# STAND_ALONE_TEST.net
KiCad netlist of a schematic drawn in EAGLE
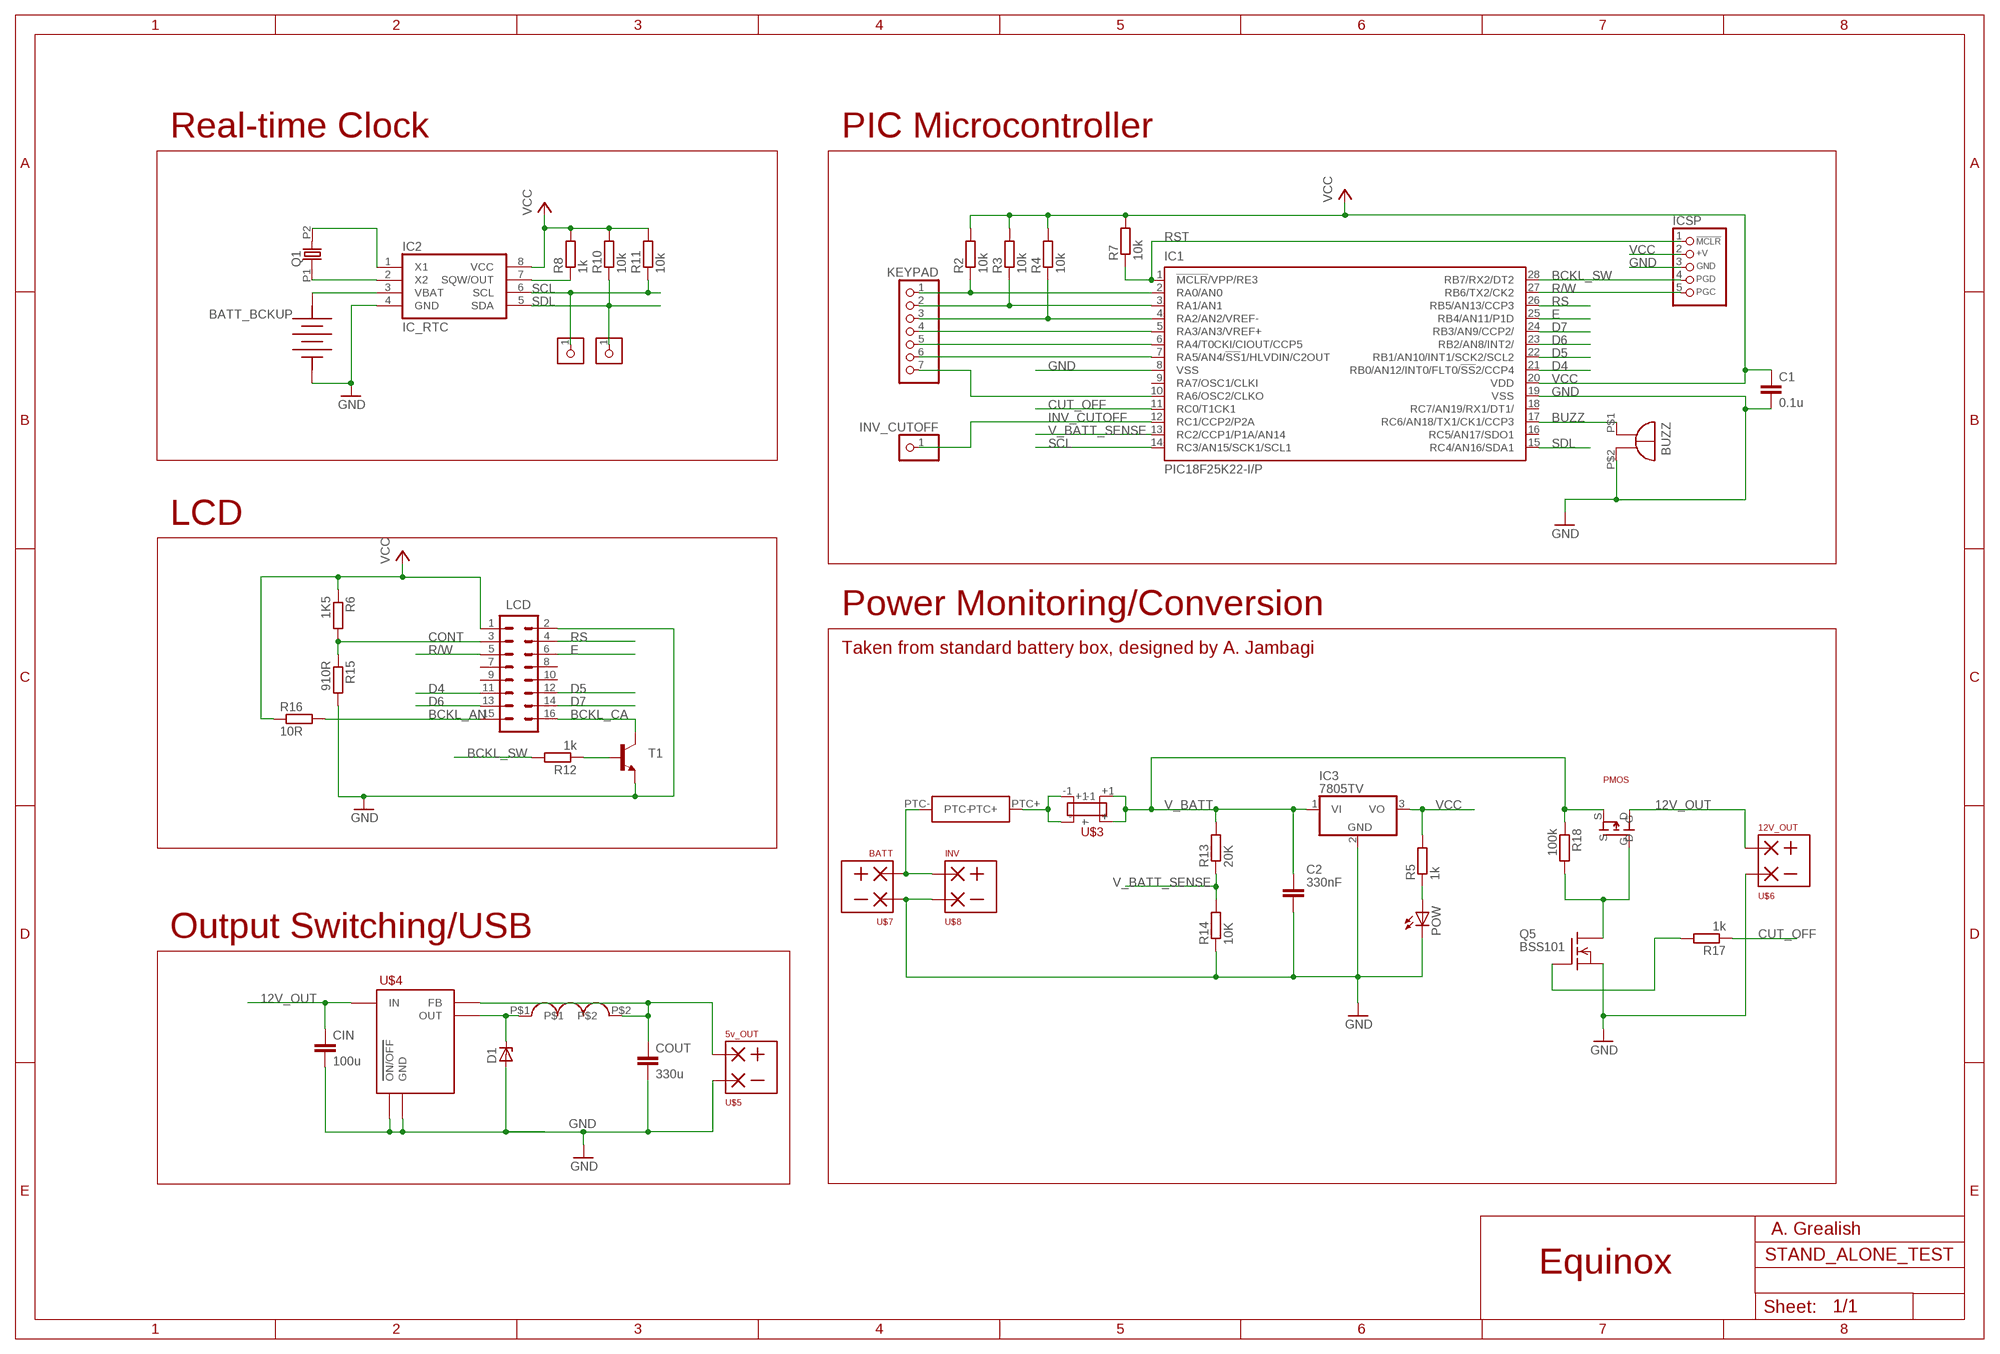
[diagram p0: schematic, sheet 1]

(export (version "E")
  (design (tool "Eeschema 10.0.6"))
  (components
    (comp (ref "BATT_BCKUP")
      (value "RENATA_COIN_CELL")
      (footprint "eagle-import:PANASONIC_CR2032_1298246")
      (libsource (lib "eagle-import") (part "PANASONIC_CR2032_1298246"))
    )
    (comp (ref "BUZZ")
      (value "BUZZ_14MM")
      (footprint "eagle-import:14MM_5M_PINS")
      (libsource (lib "eagle-import") (part "BUZZ_14MM"))
    )
    (comp (ref "C1")
      (value "0.1u")
      (footprint "eagle-import:CAP-PTH-SMALL2")
      (libsource (lib "eagle-import") (part "CAPPTH2"))
    )
    (comp (ref "C2")
      (value "330nF")
      (footprint "eagle-import:C0.1PTH")
      (libsource (lib "eagle-import") (part "CAPACITOR_NPOL-PTH_0.1{dblquote}"))
    )
    (comp (ref "CIN")
      (value "100u")
      (footprint "eagle-import:C2.5-2")
      (libsource (lib "eagle-import") (part "C2.5/2"))
    )
    (comp (ref "COUT")
      (value "330u")
      (footprint "eagle-import:C2.5-2")
      (libsource (lib "eagle-import") (part "C2.5/2"))
    )
    (comp (ref "D1")
      (value "ZENER-DIODEDO41Z10")
      (footprint "eagle-import:DO41Z10")
      (libsource (lib "eagle-import") (part "ZENER-DIODEDO41Z10"))
    )
    (comp (ref "IC1")
      (value "PIC18F25K22-I/P")
      (footprint "eagle-import:DIP28")
      (libsource (lib "eagle-import") (part "PIC18F25K22/P-I"))
    )
    (comp (ref "IC2")
      (value "IC_RTC")
      (footprint "eagle-import:DIP8")
      (libsource (lib "eagle-import") (part "IC_RTC_DS1307_DIP8"))
    )
    (comp (ref "IC3")
      (value "7805TV")
      (footprint "eagle-import:TO220V")
      (libsource (lib "eagle-import") (part "78TV05"))
    )
    (comp (ref "ICSP")
      (value "CON_HEADER_PRG_PIC_ICSPA")
      (footprint "eagle-import:HEADER_PRG_1X05")
      (libsource (lib "eagle-import") (part "CON_HEADER_PRG_PIC_ICSPA"))
    )
    (comp (ref "INV_CUTOFF")
      (value "PINHD-1X1")
      (footprint "eagle-import:1X01")
      (libsource (lib "eagle-import") (part "PINHD-1X1"))
    )
    (comp (ref "KEYPAD")
      (value "PINHD-1X7")
      (footprint "eagle-import:1X07")
      (libsource (lib "eagle-import") (part "PINHD-1X7"))
    )
    (comp (ref "LCD")
      (value "M08X2-SHROUDED_LOCK")
      (footprint "eagle-import:2X8-SHROUDED_LOCK")
      (libsource (lib "eagle-import") (part "M08X2-SHROUDED_LOCK"))
    )
    (comp (ref "PMOS")
      (value "PMOS")
      (footprint "eagle-import:NMOS_IPAK")
      (libsource (lib "eagle-import") (part "PMOS"))
    )
    (comp (ref "POW")
      (value "LED5MM")
      (footprint "eagle-import:LED5MM")
      (libsource (lib "eagle-import") (part "LED5MM"))
    )
    (comp (ref "Q1")
      (value "OSC-XTALTC-26")
      (footprint "eagle-import:TC-26")
      (libsource (lib "eagle-import") (part "OSC-XTALTC-26"))
    )
    (comp (ref "Q5")
      (value "BSS101")
      (footprint "eagle-import:TO92")
      (libsource (lib "eagle-import") (part "BSS101"))
    )
    (comp (ref "R2")
      (value "10k")
      (footprint "eagle-import:RTH025W")
      (libsource (lib "eagle-import") (part "RESISTOR-PTH-0.4"))
    )
    (comp (ref "R3")
      (value "10k")
      (footprint "eagle-import:RTH025W")
      (libsource (lib "eagle-import") (part "RESISTOR-PTH-0.4"))
    )
    (comp (ref "R4")
      (value "10k")
      (footprint "eagle-import:RTH025W")
      (libsource (lib "eagle-import") (part "RESISTOR-PTH-0.4"))
    )
    (comp (ref "R5")
      (value "1k")
      (footprint "eagle-import:RTH025W")
      (libsource (lib "eagle-import") (part "RESISTOR-PTH-0.4"))
    )
    (comp (ref "R6")
      (value "1K5")
      (footprint "eagle-import:RTH025W")
      (libsource (lib "eagle-import") (part "RESISTOR-PTH-0.4"))
    )
    (comp (ref "R7")
      (value "10k")
      (footprint "eagle-import:RTH025W")
      (libsource (lib "eagle-import") (part "RESISTOR-PTH-0.4"))
    )
    (comp (ref "R8")
      (value "1k")
      (footprint "eagle-import:RTH025W")
      (libsource (lib "eagle-import") (part "RESISTOR-PTH-0.4"))
    )
    (comp (ref "R10")
      (value "10k")
      (footprint "eagle-import:RTH025W")
      (libsource (lib "eagle-import") (part "RESISTOR-PTH-0.4"))
    )
    (comp (ref "R11")
      (value "10k")
      (footprint "eagle-import:RTH025W")
      (libsource (lib "eagle-import") (part "RESISTOR-PTH-0.4"))
    )
    (comp (ref "R12")
      (value "1k")
      (footprint "eagle-import:RTH025W")
      (libsource (lib "eagle-import") (part "RESISTOR-PTH-0.4"))
    )
    (comp (ref "R13")
      (value "20K")
      (footprint "eagle-import:RTH025W")
      (libsource (lib "eagle-import") (part "RESISTOR-PTH-0.4"))
    )
    (comp (ref "R14")
      (value "10K")
      (footprint "eagle-import:RTH025W")
      (libsource (lib "eagle-import") (part "RESISTOR-PTH-0.4"))
    )
    (comp (ref "R15")
      (value "910R")
      (footprint "eagle-import:RTH025W")
      (libsource (lib "eagle-import") (part "RESISTOR-PTH-0.4"))
    )
    (comp (ref "R16")
      (value "10R")
      (footprint "eagle-import:RTH025W")
      (libsource (lib "eagle-import") (part "RESISTOR-PTH-0.4"))
    )
    (comp (ref "R17")
      (value "1k")
      (footprint "eagle-import:RTH025W")
      (libsource (lib "eagle-import") (part "RESISTOR-PTH-0.4"))
    )
    (comp (ref "R18")
      (value "100k")
      (footprint "eagle-import:RTH025W")
      (libsource (lib "eagle-import") (part "RESISTOR-PTH-0.4"))
    )
    (comp (ref "T1")
      (value "BC546-NPN-TO92-CBE")
      (footprint "eagle-import:TO92-CBE")
      (libsource (lib "eagle-import") (part "-NPN-TO92-CBEBC546"))
    )
    (comp (ref "TP_SCL")
      (value "CON_HEADER_1X01-PTH")
      (footprint "eagle-import:M1X1")
      (libsource (lib "eagle-import") (part "CON_HEADER_1X01-PTH"))
    )
    (comp (ref "TP_SDL")
      (value "CON_HEADER_1X01-PTH")
      (footprint "eagle-import:M1X1")
      (libsource (lib "eagle-import") (part "CON_HEADER_1X01-PTH"))
    )
    (comp (ref "U$1")
      (value "EQBX_INDUCTOR2")
      (footprint "eagle-import:INDUCTOR")
      (libsource (lib "eagle-import") (part "EQBX_INDUCTOR2"))
    )
    (comp (ref "U$2")
      (value "EQBX_PTCEQBX_PTC")
      (footprint "eagle-import:EQBX_PTC")
      (libsource (lib "eagle-import") (part "EQBX_PTCEQBX_PTC"))
    )
    (comp (ref "U$3")
      (value "EQBX_FUSEEQBX_FUSE")
      (footprint "eagle-import:EQBX_FUSE")
      (libsource (lib "eagle-import") (part "EQBX_FUSEEQBX_FUSE"))
    )
    (comp (ref "U$4")
      (value "LM2575")
      (footprint "eagle-import:TO220-5")
      (libsource (lib "eagle-import") (part "LM2575"))
    )
    (comp (ref "U$5")
      (value "5v_OUT")
      (footprint "eagle-import:TERMINAL_2WAY")
      (libsource (lib "eagle-import") (part "TERMINAL_2WAY"))
    )
    (comp (ref "U$6")
      (value "12V_OUT")
      (footprint "eagle-import:TERMINAL_2WAY")
      (libsource (lib "eagle-import") (part "TERMINAL_2WAY"))
    )
    (comp (ref "U$7")
      (value "BATT")
      (footprint "eagle-import:TERMINAL_2WAY")
      (libsource (lib "eagle-import") (part "TERMINAL_2WAY"))
    )
    (comp (ref "U$8")
      (value "INV")
      (footprint "eagle-import:TERMINAL_2WAY")
      (libsource (lib "eagle-import") (part "TERMINAL_2WAY"))
    )
  )
  (nets
    (net (code "1") (name "/12V_OUT") (class "Default")
      (node (ref "CIN") (pin "1") (pinfunction "1_1") (pintype "passive"))
      (node (ref "PMOS") (pin "D") (pinfunction "D_D") (pintype "bidirectional"))
      (node (ref "U$4") (pin "P$1") (pinfunction "IN_P$1") (pintype "bidirectional"))
      (node (ref "U$6") (pin "P$1") (pinfunction "P$1_P$1") (pintype "bidirectional"))
    )
    (net (code "2") (name "/BCKL_AN") (class "Default")
      (node (ref "LCD") (pin "15") (pinfunction "15_15") (pintype "passive"))
      (node (ref "R16") (pin "2") (pinfunction "2_2") (pintype "passive"))
    )
    (net (code "3") (name "/BCKL_CA") (class "Default")
      (node (ref "LCD") (pin "16") (pinfunction "16_16") (pintype "passive"))
      (node (ref "T1") (pin "C") (pinfunction "C_C") (pintype "passive"))
    )
    (net (code "4") (name "/BCKL_SW") (class "Default")
      (node (ref "IC1") (pin "28") (pinfunction "RB7/RX2/DT2_28") (pintype "bidirectional"))
      (node (ref "ICSP") (pin "4") (pinfunction "PGD_4") (pintype "passive"))
      (node (ref "R12") (pin "2") (pinfunction "2_2") (pintype "passive"))
    )
    (net (code "5") (name "/BUZZ") (class "Default")
      (node (ref "BUZZ") (pin "P$1") (pinfunction "+_P$1") (pintype "passive"))
      (node (ref "IC1") (pin "17") (pinfunction "RC6/AN18/TX1/CK1/CCP3_17") (pintype "bidirectional"))
    )
    (net (code "6") (name "/CONT") (class "Default")
      (node (ref "LCD") (pin "3") (pinfunction "3_3") (pintype "passive"))
      (node (ref "R15") (pin "1") (pinfunction "1_1") (pintype "passive"))
      (node (ref "R6") (pin "2") (pinfunction "2_2") (pintype "passive"))
    )
    (net (code "7") (name "/CUT_OFF") (class "Default")
      (node (ref "IC1") (pin "11") (pinfunction "RC0/T1CK1_11") (pintype "bidirectional"))
      (node (ref "R17") (pin "1") (pinfunction "1_1") (pintype "passive"))
    )
    (net (code "8") (name "/D4") (class "Default")
      (node (ref "IC1") (pin "21") (pinfunction "RB0/AN12/INT0/FLT0/~{SS}2/CCP4_21") (pintype "bidirectional"))
      (node (ref "LCD") (pin "11") (pinfunction "11_11") (pintype "passive"))
    )
    (net (code "9") (name "/D5") (class "Default")
      (node (ref "IC1") (pin "22") (pinfunction "RB1/AN10/INT1/SCK2/SCL2_22") (pintype "bidirectional"))
      (node (ref "LCD") (pin "12") (pinfunction "12_12") (pintype "passive"))
    )
    (net (code "10") (name "/D6") (class "Default")
      (node (ref "IC1") (pin "23") (pinfunction "RB2/AN8/INT2/_23") (pintype "bidirectional"))
      (node (ref "LCD") (pin "13") (pinfunction "13_13") (pintype "passive"))
    )
    (net (code "11") (name "/D7") (class "Default")
      (node (ref "IC1") (pin "24") (pinfunction "RB3/AN9/CCP2/_24") (pintype "bidirectional"))
      (node (ref "LCD") (pin "14") (pinfunction "14_14") (pintype "passive"))
    )
    (net (code "12") (name "/E") (class "Default")
      (node (ref "IC1") (pin "25") (pinfunction "RB4/AN11/P1D_25") (pintype "bidirectional"))
      (node (ref "LCD") (pin "6") (pinfunction "6_6") (pintype "passive"))
    )
    (net (code "13") (name "/INV_CUTOFF") (class "Default")
      (node (ref "IC1") (pin "12") (pinfunction "RC1/CCP2/P2A_12") (pintype "bidirectional"))
      (node (ref "INV_CUTOFF") (pin "1") (pinfunction "1_1") (pintype "passive"))
    )
    (net (code "14") (name "/RS") (class "Default")
      (node (ref "IC1") (pin "26") (pinfunction "RB5/AN13/CCP3_26") (pintype "bidirectional"))
      (node (ref "LCD") (pin "4") (pinfunction "4_4") (pintype "passive"))
    )
    (net (code "15") (name "/RST") (class "Default")
      (node (ref "IC1") (pin "1") (pinfunction "~{MCLR}/VPP/RE3_1") (pintype "input"))
      (node (ref "ICSP") (pin "1") (pinfunction "/MCLR_1") (pintype "passive"))
      (node (ref "R7") (pin "1") (pinfunction "1_1") (pintype "passive"))
    )
    (net (code "16") (name "/R{slash}W") (class "Default")
      (node (ref "IC1") (pin "27") (pinfunction "RB6/TX2/CK2_27") (pintype "bidirectional"))
      (node (ref "ICSP") (pin "5") (pinfunction "PGC_5") (pintype "passive"))
      (node (ref "LCD") (pin "5") (pinfunction "5_5") (pintype "passive"))
    )
    (net (code "17") (name "/SCL") (class "Default")
      (node (ref "IC1") (pin "14") (pinfunction "RC3/AN15/SCK1/SCL1_14") (pintype "bidirectional"))
      (node (ref "IC2") (pin "6") (pinfunction "SCL_6") (pintype "bidirectional"))
      (node (ref "R11") (pin "1") (pinfunction "1_1") (pintype "passive"))
      (node (ref "TP_SCL") (pin "1") (pinfunction "1_1") (pintype "passive"))
    )
    (net (code "18") (name "/SDL") (class "Default")
      (node (ref "IC1") (pin "15") (pinfunction "RC4/AN16/SDA1_15") (pintype "bidirectional"))
      (node (ref "IC2") (pin "5") (pinfunction "SDA_5") (pintype "bidirectional"))
      (node (ref "R10") (pin "1") (pinfunction "1_1") (pintype "passive"))
      (node (ref "TP_SDL") (pin "1") (pinfunction "1_1") (pintype "passive"))
    )
    (net (code "19") (name "/V_BATT") (class "Default")
      (node (ref "C2") (pin "1") (pinfunction "1_1") (pintype "passive"))
      (node (ref "IC3") (pin "1") (pinfunction "VI_1") (pintype "input"))
      (node (ref "PMOS") (pin "S") (pinfunction "S_S") (pintype "bidirectional"))
      (node (ref "R13") (pin "2") (pinfunction "2_2") (pintype "passive"))
      (node (ref "R18") (pin "1") (pinfunction "1_1") (pintype "passive"))
      (node (ref "U$3") (pin "+") (pinfunction "+_+") (pintype "bidirectional"))
      (node (ref "U$3") (pin "+1") (pinfunction "+1_+1") (pintype "bidirectional"))
    )
    (net (code "20") (name "/V_BATT_SENSE") (class "Default")
      (node (ref "IC1") (pin "13") (pinfunction "RC2/CCP1/P1A/AN14_13") (pintype "bidirectional"))
      (node (ref "R13") (pin "1") (pinfunction "1_1") (pintype "passive"))
      (node (ref "R14") (pin "2") (pinfunction "2_2") (pintype "passive"))
    )
    (net (code "21") (name "GND") (class "Default")
      (node (ref "BATT_BCKUP") (pin "P-") (pinfunction "NEG_P-") (pintype "bidirectional"))
      (node (ref "BUZZ") (pin "P$2") (pinfunction "-_P$2") (pintype "passive"))
      (node (ref "C1") (pin "2") (pinfunction "2_2") (pintype "passive"))
      (node (ref "C2") (pin "2") (pinfunction "2_2") (pintype "passive"))
      (node (ref "CIN") (pin "2") (pinfunction "2_2") (pintype "passive"))
      (node (ref "COUT") (pin "2") (pinfunction "2_2") (pintype "passive"))
      (node (ref "D1") (pin "A") (pinfunction "A_A") (pintype "passive"))
      (node (ref "IC1") (pin "19") (pinfunction "VSS_19") (pintype "power_in"))
      (node (ref "IC1") (pin "8") (pinfunction "VSS_8") (pintype "power_in"))
      (node (ref "IC2") (pin "4") (pinfunction "GND_4") (pintype "bidirectional"))
      (node (ref "IC3") (pin "2") (pinfunction "GND_2") (pintype "passive"))
      (node (ref "ICSP") (pin "3") (pinfunction "GND_3") (pintype "passive"))
      (node (ref "LCD") (pin "2") (pinfunction "2_2") (pintype "passive"))
      (node (ref "POW") (pin "K") (pinfunction "C_K") (pintype "passive"))
      (node (ref "Q5") (pin "1") (pinfunction "S_1") (pintype "passive"))
      (node (ref "R14") (pin "1") (pinfunction "1_1") (pintype "passive"))
      (node (ref "R15") (pin "2") (pinfunction "2_2") (pintype "passive"))
      (node (ref "T1") (pin "E") (pinfunction "E_E") (pintype "passive"))
      (node (ref "U$4") (pin "P$3") (pinfunction "GND_P$3") (pintype "bidirectional"))
      (node (ref "U$4") (pin "P$5") (pinfunction "ON/OFF_P$5") (pintype "bidirectional"))
      (node (ref "U$5") (pin "P$2") (pinfunction "P$2_P$2") (pintype "bidirectional"))
      (node (ref "U$6") (pin "P$2") (pinfunction "P$2_P$2") (pintype "bidirectional"))
      (node (ref "U$7") (pin "P$2") (pinfunction "P$2_P$2") (pintype "bidirectional"))
      (node (ref "U$8") (pin "P$2") (pinfunction "P$2_P$2") (pintype "bidirectional"))
    )
    (net (code "22") (name "Net-(BATT_BCKUP-POS)") (class "Default")
      (node (ref "BATT_BCKUP") (pin "P+") (pinfunction "POS_P+") (pintype "bidirectional"))
      (node (ref "IC2") (pin "3") (pinfunction "VBAT_3") (pintype "bidirectional"))
    )
    (net (code "23") (name "Net-(IC1-RA0{slash}AN0)") (class "Default")
      (node (ref "IC1") (pin "2") (pinfunction "RA0/AN0_2") (pintype "bidirectional"))
      (node (ref "KEYPAD") (pin "1") (pinfunction "1_1") (pintype "passive"))
      (node (ref "R2") (pin "1") (pinfunction "1_1") (pintype "passive"))
    )
    (net (code "24") (name "Net-(IC1-RA1{slash}AN1)") (class "Default")
      (node (ref "IC1") (pin "3") (pinfunction "RA1/AN1_3") (pintype "bidirectional"))
      (node (ref "KEYPAD") (pin "2") (pinfunction "2_2") (pintype "passive"))
      (node (ref "R3") (pin "1") (pinfunction "1_1") (pintype "passive"))
    )
    (net (code "25") (name "Net-(IC1-RA2{slash}AN2{slash}VREF-)") (class "Default")
      (node (ref "IC1") (pin "4") (pinfunction "RA2/AN2/VREF-_4") (pintype "bidirectional"))
      (node (ref "KEYPAD") (pin "3") (pinfunction "3_3") (pintype "passive"))
      (node (ref "R4") (pin "1") (pinfunction "1_1") (pintype "passive"))
    )
    (net (code "26") (name "Net-(IC1-RA3{slash}AN3{slash}VREF+)") (class "Default")
      (node (ref "IC1") (pin "5") (pinfunction "RA3/AN3/VREF+_5") (pintype "bidirectional"))
      (node (ref "KEYPAD") (pin "4") (pinfunction "4_4") (pintype "passive"))
    )
    (net (code "27") (name "Net-(IC1-RA4{slash}T0CKI{slash}CIOUT{slash}CCP5)") (class "Default")
      (node (ref "IC1") (pin "6") (pinfunction "RA4/T0CKI/CIOUT/CCP5_6") (pintype "bidirectional"))
      (node (ref "KEYPAD") (pin "5") (pinfunction "5_5") (pintype "passive"))
    )
    (net (code "28") (name "Net-(IC1-RA5{slash}AN4{slash}~{SS}1{slash}HLVDIN{slash}C2OUT)") (class "Default")
      (node (ref "IC1") (pin "7") (pinfunction "RA5/AN4/~{SS}1/HLVDIN/C2OUT_7") (pintype "bidirectional"))
      (node (ref "KEYPAD") (pin "6") (pinfunction "6_6") (pintype "passive"))
    )
    (net (code "29") (name "Net-(IC1-RA6{slash}OSC2{slash}CLKO)") (class "Default")
      (node (ref "IC1") (pin "10") (pinfunction "RA6/OSC2/CLKO_10") (pintype "output"))
      (node (ref "KEYPAD") (pin "7") (pinfunction "7_7") (pintype "passive"))
    )
    (net (code "30") (name "Net-(IC2-SQW{slash}OUT)") (class "Default")
      (node (ref "IC2") (pin "7") (pinfunction "SQW/OUT_7") (pintype "bidirectional"))
      (node (ref "R8") (pin "1") (pinfunction "1_1") (pintype "passive"))
    )
    (net (code "31") (name "Net-(IC2-X1)") (class "Default")
      (node (ref "IC2") (pin "1") (pinfunction "X1_1") (pintype "bidirectional"))
      (node (ref "Q1") (pin "P2") (pinfunction "2_P2") (pintype "passive"))
    )
    (net (code "32") (name "Net-(IC2-X2)") (class "Default")
      (node (ref "IC2") (pin "2") (pinfunction "X2_2") (pintype "bidirectional"))
      (node (ref "Q1") (pin "P1") (pinfunction "1_P1") (pintype "passive"))
    )
    (net (code "33") (name "Net-(POW-PadA)") (class "Default")
      (node (ref "POW") (pin "A") (pinfunction "A_A") (pintype "passive"))
      (node (ref "R5") (pin "1") (pinfunction "1_1") (pintype "passive"))
    )
    (net (code "34") (name "Net-(Q5-D)") (class "Default")
      (node (ref "PMOS") (pin "G") (pinfunction "G_G") (pintype "bidirectional"))
      (node (ref "Q5") (pin "3") (pinfunction "D_3") (pintype "passive"))
      (node (ref "R18") (pin "2") (pinfunction "2_2") (pintype "passive"))
    )
    (net (code "35") (name "Net-(Q5-G)") (class "Default")
      (node (ref "Q5") (pin "2") (pinfunction "G_2") (pintype "passive"))
      (node (ref "R17") (pin "2") (pinfunction "2_2") (pintype "passive"))
    )
    (net (code "36") (name "Net-(R12-Pad1)") (class "Default")
      (node (ref "R12") (pin "1") (pinfunction "1_1") (pintype "passive"))
      (node (ref "T1") (pin "B") (pinfunction "B_B") (pintype "passive"))
    )
    (net (code "37") (name "Net-(U$2-PadPTC+)") (class "Default")
      (node (ref "U$2") (pin "PTC+") (pinfunction "PTC+_PTC+") (pintype "bidirectional"))
      (node (ref "U$3") (pin "-") (pinfunction "-_-") (pintype "bidirectional"))
      (node (ref "U$3") (pin "-1") (pinfunction "-1_-1") (pintype "bidirectional"))
    )
    (net (code "38") (name "Net-(U$2-PadPTC-)") (class "Default")
      (node (ref "U$2") (pin "PTC-") (pinfunction "PTC-_PTC-") (pintype "bidirectional"))
      (node (ref "U$7") (pin "P$1") (pinfunction "P$1_P$1") (pintype "bidirectional"))
      (node (ref "U$8") (pin "P$1") (pinfunction "P$1_P$1") (pintype "bidirectional"))
    )
    (net (code "39") (name "Net-(U$4-FB)") (class "Default")
      (node (ref "COUT") (pin "1") (pinfunction "1_1") (pintype "passive"))
      (node (ref "U$1") (pin "P$2") (pinfunction "P$2_P$2") (pintype "bidirectional"))
      (node (ref "U$4") (pin "P$4") (pinfunction "FB_P$4") (pintype "bidirectional"))
      (node (ref "U$5") (pin "P$1") (pinfunction "P$1_P$1") (pintype "bidirectional"))
    )
    (net (code "40") (name "Net-(U$4-OUT)") (class "Default")
      (node (ref "D1") (pin "C") (pinfunction "C_C") (pintype "passive"))
      (node (ref "U$1") (pin "P$1") (pinfunction "P$1_P$1") (pintype "bidirectional"))
      (node (ref "U$4") (pin "P$2") (pinfunction "OUT_P$2") (pintype "bidirectional"))
    )
    (net (code "41") (name "VCC") (class "Default")
      (node (ref "C1") (pin "1") (pinfunction "1_1") (pintype "passive"))
      (node (ref "IC1") (pin "20") (pinfunction "VDD_20") (pintype "power_in"))
      (node (ref "IC2") (pin "8") (pinfunction "VCC_8") (pintype "bidirectional"))
      (node (ref "IC3") (pin "3") (pinfunction "VO_3") (pintype "passive"))
      (node (ref "ICSP") (pin "2") (pinfunction "+V_2") (pintype "passive"))
      (node (ref "LCD") (pin "1") (pinfunction "1_1") (pintype "passive"))
      (node (ref "R10") (pin "2") (pinfunction "2_2") (pintype "passive"))
      (node (ref "R11") (pin "2") (pinfunction "2_2") (pintype "passive"))
      (node (ref "R16") (pin "1") (pinfunction "1_1") (pintype "passive"))
      (node (ref "R2") (pin "2") (pinfunction "2_2") (pintype "passive"))
      (node (ref "R3") (pin "2") (pinfunction "2_2") (pintype "passive"))
      (node (ref "R4") (pin "2") (pinfunction "2_2") (pintype "passive"))
      (node (ref "R5") (pin "2") (pinfunction "2_2") (pintype "passive"))
      (node (ref "R6") (pin "1") (pinfunction "1_1") (pintype "passive"))
      (node (ref "R7") (pin "2") (pinfunction "2_2") (pintype "passive"))
      (node (ref "R8") (pin "2") (pinfunction "2_2") (pintype "passive"))
    )
    (net (code "42") (name "unconnected-(IC1-RA7{slash}OSC1{slash}CLKI-Pad9)") (class "Default")
      (node (ref "IC1") (pin "9") (pinfunction "RA7/OSC1/CLKI_9") (pintype "input"))
    )
    (net (code "43") (name "unconnected-(IC1-RC5{slash}AN17{slash}SDO1-Pad16)") (class "Default")
      (node (ref "IC1") (pin "16") (pinfunction "RC5/AN17/SDO1_16") (pintype "bidirectional"))
    )
    (net (code "44") (name "unconnected-(IC1-RC7{slash}AN19{slash}RX1{slash}DT1{slash}-Pad18)") (class "Default")
      (node (ref "IC1") (pin "18") (pinfunction "RC7/AN19/RX1/DT1/_18") (pintype "bidirectional"))
    )
    (net (code "45") (name "unconnected-(LCD-Pad7)") (class "Default")
      (node (ref "LCD") (pin "7") (pinfunction "7_7") (pintype "passive"))
    )
    (net (code "46") (name "unconnected-(LCD-Pad8)") (class "Default")
      (node (ref "LCD") (pin "8") (pinfunction "8_8") (pintype "passive"))
    )
    (net (code "47") (name "unconnected-(LCD-Pad9)") (class "Default")
      (node (ref "LCD") (pin "9") (pinfunction "9_9") (pintype "passive"))
    )
    (net (code "48") (name "unconnected-(LCD-Pad10)") (class "Default")
      (node (ref "LCD") (pin "10") (pinfunction "10_10") (pintype "passive"))
    )
  )
)
